# tex-v0.net
KiCad netlist of a schematic drawn in EAGLE
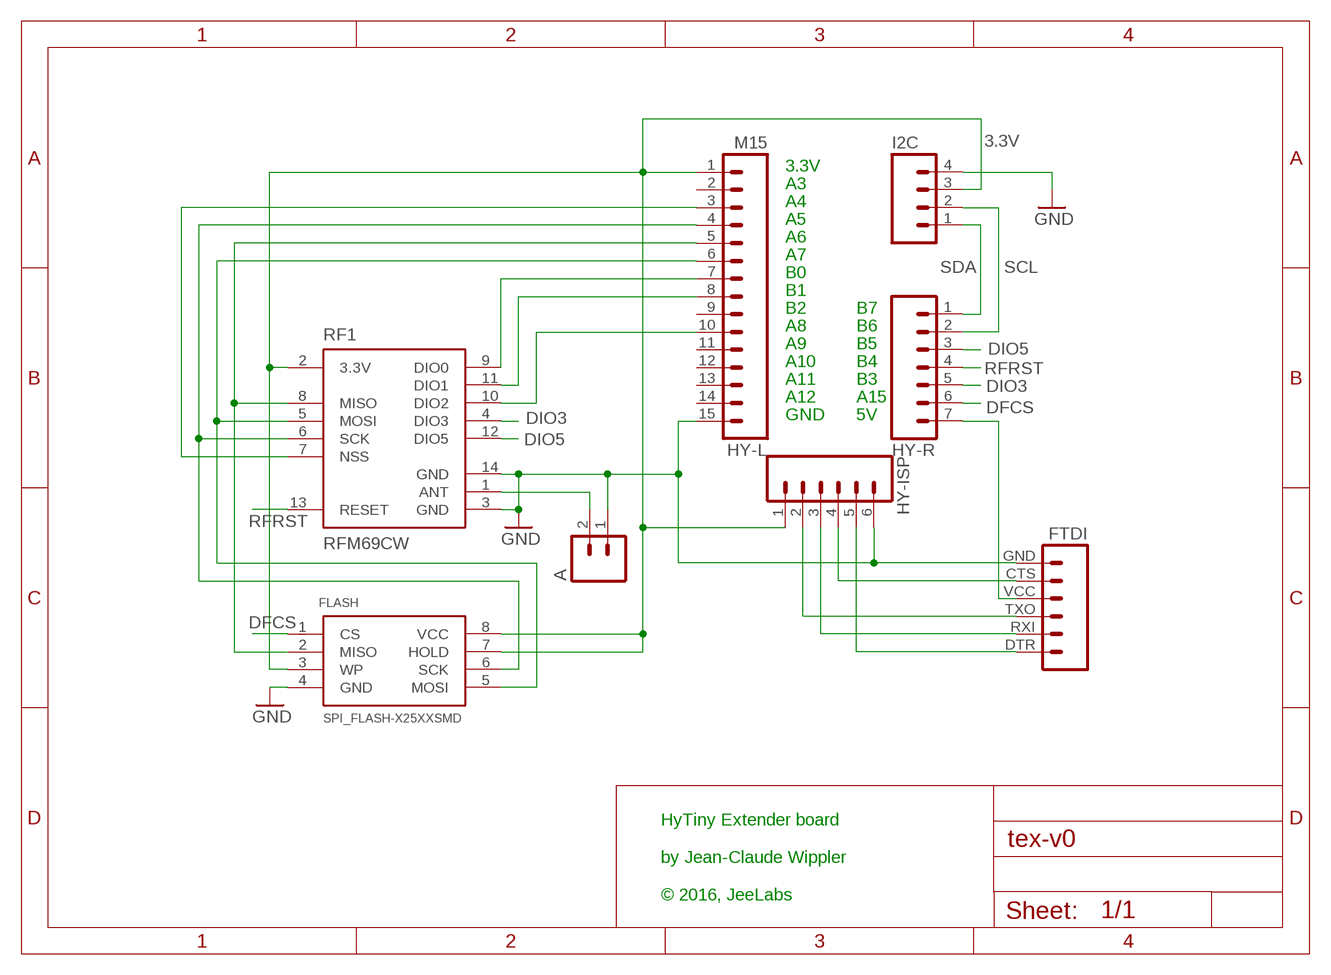
[diagram p0: schematic, sheet 1]

(export (version "E")
  (design (tool "Eeschema 10.0.6"))
  (components
    (comp (ref "A")
      (value "M021X02_NO_SILK")
      (footprint "eagle-import:1X02_NO_SILK")
      (libsource (lib "eagle-import") (part "M021X02_NO_SILK"))
    )
    (comp (ref "FLASH")
      (value "SPI_FLASH-X25XXSMD")
      (footprint "eagle-import:SO08")
      (libsource (lib "eagle-import") (part "SPI_FLASH-X25XXSMD"))
    )
    (comp (ref "FTDI")
      (value "FTDI_BASICPTH")
      (footprint "eagle-import:FTDI_BASIC")
      (libsource (lib "eagle-import") (part "FTDI_BASICPTH"))
    )
    (comp (ref "HY-ISP")
      (value "M06NO_SILK_FEMALE_PTH")
      (footprint "eagle-import:1X06_NO_SILK")
      (libsource (lib "eagle-import") (part "M06NO_SILK_FEMALE_PTH"))
    )
    (comp (ref "HY-L")
      (value "M15")
      (footprint "eagle-import:1X15")
      (libsource (lib "eagle-import") (part "M15"))
    )
    (comp (ref "HY-R")
      (value "M07")
      (footprint "eagle-import:1X07")
      (libsource (lib "eagle-import") (part "M07"))
    )
    (comp (ref "I2C")
      (value "M041X04_NO_SILK")
      (footprint "eagle-import:1X04_NO_SILK")
      (libsource (lib "eagle-import") (part "M041X04_NO_SILK"))
    )
    (comp (ref "RF1")
      (value "RFM69CW")
      (footprint "eagle-import:RFM69CW-XXXS2")
      (libsource (lib "eagle-import") (part "RFM69CW"))
    )
  )
  (nets
    (net (code "1") (name "/3.3V") (class "Default")
      (node (ref "FLASH") (pin "3") (pinfunction "WP_3") (pintype "bidirectional"))
      (node (ref "FLASH") (pin "7") (pinfunction "HOLD_7") (pintype "bidirectional"))
      (node (ref "FLASH") (pin "8") (pinfunction "VCC_8") (pintype "bidirectional"))
      (node (ref "HY-ISP") (pin "1") (pinfunction "1_1") (pintype "passive"))
      (node (ref "HY-L") (pin "1") (pinfunction "1_1") (pintype "passive"))
      (node (ref "I2C") (pin "3") (pinfunction "3_3") (pintype "passive"))
      (node (ref "RF1") (pin "2") (pinfunction "3.3V_2") (pintype "power_in"))
    )
    (net (code "2") (name "/DFCS") (class "Default")
      (node (ref "FLASH") (pin "1") (pinfunction "CS_1") (pintype "bidirectional"))
      (node (ref "HY-R") (pin "6") (pinfunction "6_6") (pintype "passive"))
    )
    (net (code "3") (name "/DIO3") (class "Default")
      (node (ref "HY-R") (pin "5") (pinfunction "5_5") (pintype "passive"))
      (node (ref "RF1") (pin "4") (pinfunction "DIO3_4") (pintype "bidirectional"))
    )
    (net (code "4") (name "/DIO5") (class "Default")
      (node (ref "HY-R") (pin "3") (pinfunction "3_3") (pintype "passive"))
      (node (ref "RF1") (pin "12") (pinfunction "DIO5_12") (pintype "bidirectional"))
    )
    (net (code "5") (name "/RFRST") (class "Default")
      (node (ref "HY-R") (pin "4") (pinfunction "4_4") (pintype "passive"))
      (node (ref "RF1") (pin "13") (pinfunction "RESET_13") (pintype "input"))
    )
    (net (code "6") (name "/SCL") (class "Default")
      (node (ref "HY-R") (pin "2") (pinfunction "2_2") (pintype "passive"))
      (node (ref "I2C") (pin "2") (pinfunction "2_2") (pintype "passive"))
    )
    (net (code "7") (name "/SDA") (class "Default")
      (node (ref "HY-R") (pin "1") (pinfunction "1_1") (pintype "passive"))
      (node (ref "I2C") (pin "1") (pinfunction "1_1") (pintype "passive"))
    )
    (net (code "8") (name "GND") (class "Default")
      (node (ref "A") (pin "1") (pinfunction "1_1") (pintype "passive"))
      (node (ref "FLASH") (pin "4") (pinfunction "GND_4") (pintype "bidirectional"))
      (node (ref "FTDI") (pin "GND") (pinfunction "6_GND") (pintype "passive"))
      (node (ref "HY-ISP") (pin "6") (pinfunction "6_6") (pintype "passive"))
      (node (ref "HY-L") (pin "15") (pinfunction "15_15") (pintype "passive"))
      (node (ref "I2C") (pin "4") (pinfunction "4_4") (pintype "passive"))
      (node (ref "RF1") (pin "14") (pinfunction "GND_14") (pintype "power_in"))
      (node (ref "RF1") (pin "3") (pinfunction "GND_3") (pintype "power_in"))
    )
    (net (code "9") (name "Net-(FLASH-MISO)") (class "Default")
      (node (ref "FLASH") (pin "2") (pinfunction "MISO_2") (pintype "bidirectional"))
      (node (ref "HY-L") (pin "5") (pinfunction "5_5") (pintype "passive"))
      (node (ref "RF1") (pin "8") (pinfunction "MISO_8") (pintype "bidirectional"))
    )
    (net (code "10") (name "Net-(FLASH-MOSI)") (class "Default")
      (node (ref "FLASH") (pin "5") (pinfunction "MOSI_5") (pintype "bidirectional"))
      (node (ref "HY-L") (pin "6") (pinfunction "6_6") (pintype "passive"))
      (node (ref "RF1") (pin "5") (pinfunction "MOSI_5") (pintype "input"))
    )
    (net (code "11") (name "Net-(FLASH-SCK)") (class "Default")
      (node (ref "FLASH") (pin "6") (pinfunction "SCK_6") (pintype "bidirectional"))
      (node (ref "HY-L") (pin "4") (pinfunction "4_4") (pintype "passive"))
      (node (ref "RF1") (pin "6") (pinfunction "SCK_6") (pintype "input"))
    )
    (net (code "12") (name "Net-(FTDI-1)") (class "Default")
      (node (ref "FTDI") (pin "DTR") (pinfunction "1_DTR") (pintype "passive"))
      (node (ref "HY-ISP") (pin "5") (pinfunction "5_5") (pintype "passive"))
    )
    (net (code "13") (name "Net-(FTDI-2)") (class "Default")
      (node (ref "FTDI") (pin "RXI") (pinfunction "2_RXI") (pintype "passive"))
      (node (ref "HY-ISP") (pin "3") (pinfunction "3_3") (pintype "passive"))
    )
    (net (code "14") (name "Net-(FTDI-3)") (class "Default")
      (node (ref "FTDI") (pin "TXO") (pinfunction "3_TXO") (pintype "passive"))
      (node (ref "HY-ISP") (pin "2") (pinfunction "2_2") (pintype "passive"))
    )
    (net (code "15") (name "Net-(FTDI-4)") (class "Default")
      (node (ref "FTDI") (pin "VCC") (pinfunction "4_VCC") (pintype "passive"))
      (node (ref "HY-R") (pin "7") (pinfunction "7_7") (pintype "passive"))
    )
    (net (code "16") (name "Net-(FTDI-5)") (class "Default")
      (node (ref "FTDI") (pin "CTS") (pinfunction "5_CTS") (pintype "passive"))
      (node (ref "HY-ISP") (pin "4") (pinfunction "4_4") (pintype "passive"))
    )
    (net (code "17") (name "Net-(RF1-ANT)") (class "Default")
      (node (ref "A") (pin "2") (pinfunction "2_2") (pintype "passive"))
      (node (ref "RF1") (pin "1") (pinfunction "ANT_1") (pintype "passive"))
    )
    (net (code "18") (name "Net-(RF1-DIO0)") (class "Default")
      (node (ref "HY-L") (pin "7") (pinfunction "7_7") (pintype "passive"))
      (node (ref "RF1") (pin "9") (pinfunction "DIO0_9") (pintype "bidirectional"))
    )
    (net (code "19") (name "Net-(RF1-DIO1)") (class "Default")
      (node (ref "HY-L") (pin "8") (pinfunction "8_8") (pintype "passive"))
      (node (ref "RF1") (pin "11") (pinfunction "DIO1_11") (pintype "bidirectional"))
    )
    (net (code "20") (name "Net-(RF1-DIO2)") (class "Default")
      (node (ref "HY-L") (pin "10") (pinfunction "10_10") (pintype "passive"))
      (node (ref "RF1") (pin "10") (pinfunction "DIO2_10") (pintype "bidirectional"))
    )
    (net (code "21") (name "Net-(RF1-NSS)") (class "Default")
      (node (ref "HY-L") (pin "3") (pinfunction "3_3") (pintype "passive"))
      (node (ref "RF1") (pin "7") (pinfunction "NSS_7") (pintype "input"))
    )
    (net (code "22") (name "unconnected-(HY-L-Pad2)") (class "Default")
      (node (ref "HY-L") (pin "2") (pinfunction "2_2") (pintype "passive"))
    )
    (net (code "23") (name "unconnected-(HY-L-Pad9)") (class "Default")
      (node (ref "HY-L") (pin "9") (pinfunction "9_9") (pintype "passive"))
    )
    (net (code "24") (name "unconnected-(HY-L-Pad11)") (class "Default")
      (node (ref "HY-L") (pin "11") (pinfunction "11_11") (pintype "passive"))
    )
    (net (code "25") (name "unconnected-(HY-L-Pad12)") (class "Default")
      (node (ref "HY-L") (pin "12") (pinfunction "12_12") (pintype "passive"))
    )
    (net (code "26") (name "unconnected-(HY-L-Pad13)") (class "Default")
      (node (ref "HY-L") (pin "13") (pinfunction "13_13") (pintype "passive"))
    )
    (net (code "27") (name "unconnected-(HY-L-Pad14)") (class "Default")
      (node (ref "HY-L") (pin "14") (pinfunction "14_14") (pintype "passive"))
    )
  )
)
